# PMIC.net
KiCad netlist of a schematic drawn in Altium Designer
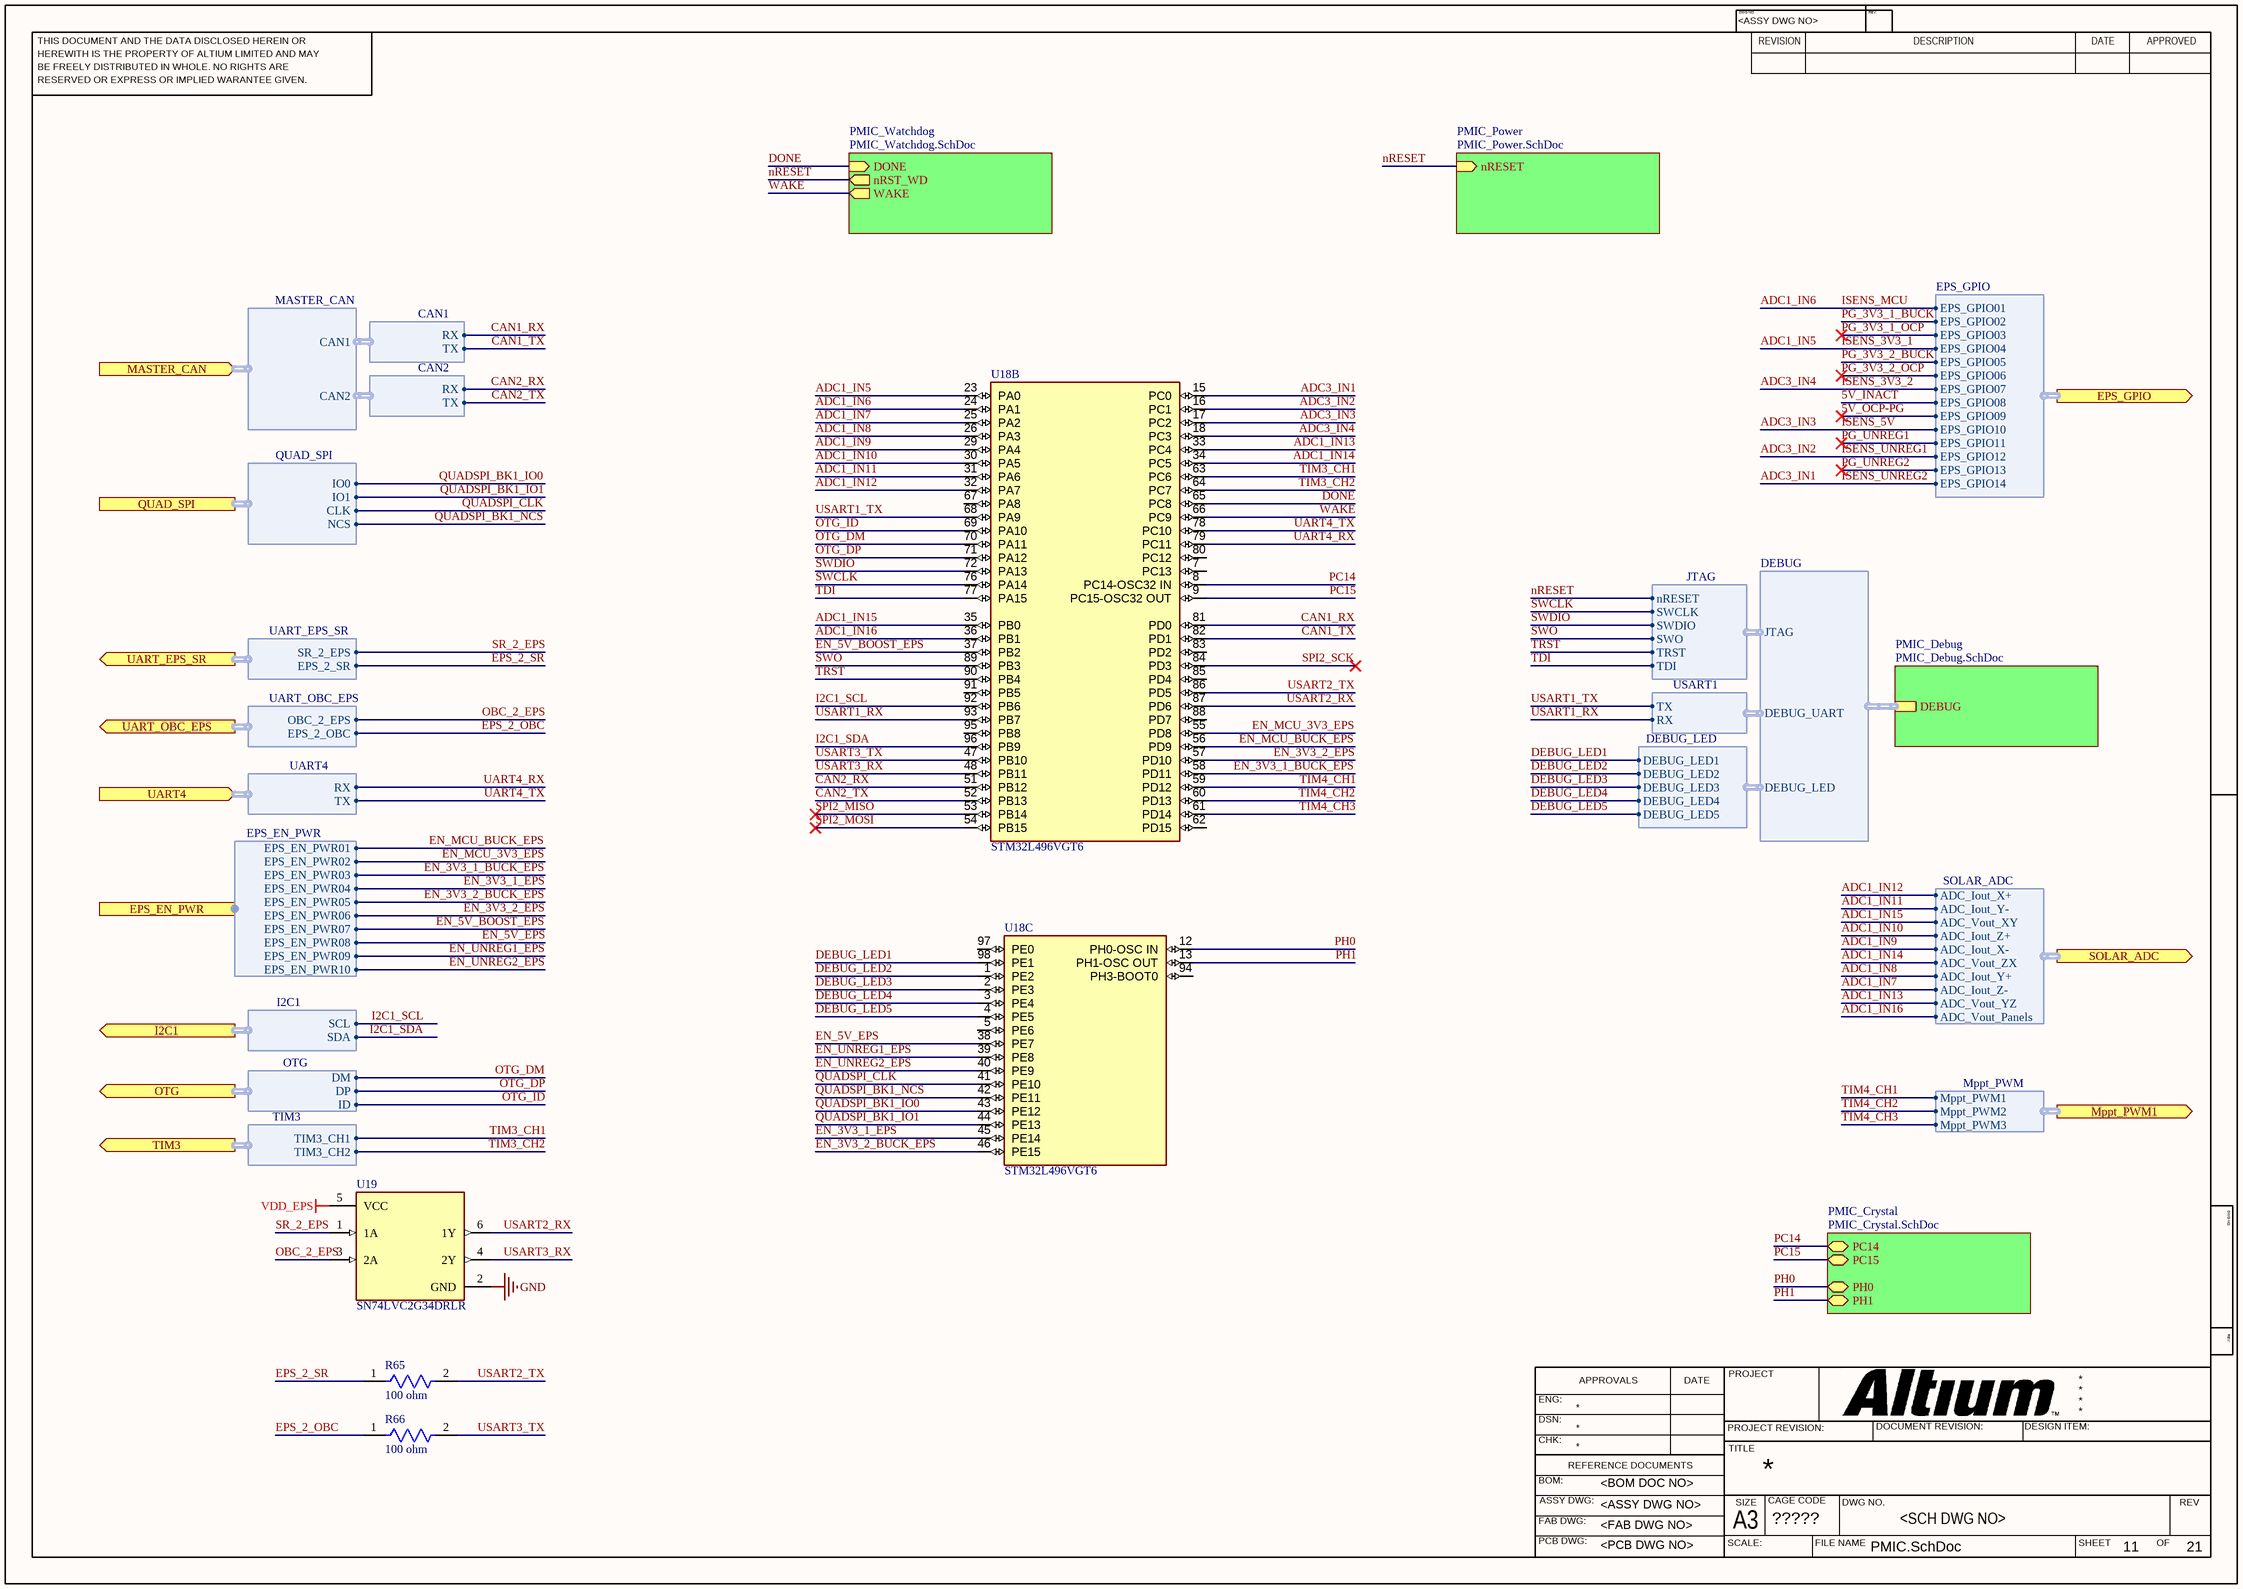
[diagram p0: PMIC.SchDoc]

(export (version "E")
  (design (tool "Eeschema 10.0.6"))
  (components
    (comp (ref "R65")
      (value "100 ohm")
      (footprint "FP-ERJP03-MFG")
      (description "ERJ-P03F1000V SMD Chip Resistor, 100 Ohm, ± 1%, 200 mW, 0603 [1608 Metric], Thick Film, Anti-Surge")
      (fields (field (name "TOLERANCE") "1%"))
      (libsource (lib "Altium Content Vault") (part "1029c3af85768c4190bb7ad29bc67b5"))
    )
    (comp (ref "R66")
      (value "100 ohm")
      (footprint "FP-ERJP03-MFG")
      (description "ERJ-P03F1000V SMD Chip Resistor, 100 Ohm, ± 1%, 200 mW, 0603 [1608 Metric], Thick Film, Anti-Surge")
      (fields (field (name "TOLERANCE") "1%"))
      (libsource (lib "Altium Content Vault") (part "1029c3af85768c4190bb7ad29bc67b5"))
    )
    (comp (ref "U18")
      (value "STM32L496VGT6")
      (footprint "FP-LQFP100-1L-MFG")
      (description "IC MCU 32BIT 1MB FLASH 100LQFP")
      (fields
        (field (name "MANUFACTURER") "STMicroelectronics")
        (field (name "OCTOPART") "https://octopart.com/stm32l496vgt6-stmicroelectronics-80826723")
      )
      (libsource (lib "Altium Content Vault") (part "c3654b0af0513536dfc3423c68ccd0e"))
    )
    (comp (ref "U19")
      (value "SN74LVC2G34DRLR")
      (footprint "FP-DRL0006A-MFG")
      (description "IC BUFFER NON-INVERT 5.5V 6SOT")
      (libsource (lib "Altium Content Vault") (part "59303bce76f5fafbc101ba271662c75"))
    )
  )
  (nets
    (net (code "21") (name "/ADC1_IN5") (class "Default")
      (node (ref "U18") (pin "23") (pinfunction "PA0_23") (pintype "bidirectional"))
    )
    (net (code "22") (name "/ADC1_IN6") (class "Default")
      (node (ref "U18") (pin "24") (pinfunction "PA1_24") (pintype "bidirectional"))
    )
    (net (code "23") (name "/ADC1_IN7") (class "Default")
      (node (ref "U18") (pin "25") (pinfunction "PA2_25") (pintype "bidirectional"))
    )
    (net (code "24") (name "/ADC1_IN8") (class "Default")
      (node (ref "U18") (pin "26") (pinfunction "PA3_26") (pintype "bidirectional"))
    )
    (net (code "25") (name "/ADC1_IN9") (class "Default")
      (node (ref "U18") (pin "29") (pinfunction "PA4_29") (pintype "bidirectional"))
    )
    (net (code "26") (name "/ADC1_IN10") (class "Default")
      (node (ref "U18") (pin "30") (pinfunction "PA5_30") (pintype "bidirectional"))
    )
    (net (code "27") (name "/ADC1_IN11") (class "Default")
      (node (ref "U18") (pin "31") (pinfunction "PA6_31") (pintype "bidirectional"))
    )
    (net (code "28") (name "/ADC1_IN12") (class "Default")
      (node (ref "U18") (pin "32") (pinfunction "PA7_32") (pintype "bidirectional"))
    )
    (net (code "29") (name "/ADC1_IN13") (class "Default")
      (node (ref "U18") (pin "33") (pinfunction "PC4_33") (pintype "bidirectional"))
    )
    (net (code "30") (name "/ADC1_IN14") (class "Default")
      (node (ref "U18") (pin "34") (pinfunction "PC5_34") (pintype "bidirectional"))
    )
    (net (code "31") (name "/ADC1_IN15") (class "Default")
      (node (ref "U18") (pin "35") (pinfunction "PB0_35") (pintype "bidirectional"))
    )
    (net (code "32") (name "/ADC1_IN16") (class "Default")
      (node (ref "U18") (pin "36") (pinfunction "PB1_36") (pintype "bidirectional"))
    )
    (net (code "33") (name "/ADC3_IN1") (class "Default")
      (node (ref "U18") (pin "15") (pinfunction "PC0_15") (pintype "bidirectional"))
    )
    (net (code "34") (name "/ADC3_IN2") (class "Default")
      (node (ref "U18") (pin "16") (pinfunction "PC1_16") (pintype "bidirectional"))
    )
    (net (code "35") (name "/ADC3_IN3") (class "Default")
      (node (ref "U18") (pin "17") (pinfunction "PC2_17") (pintype "bidirectional"))
    )
    (net (code "36") (name "/ADC3_IN4") (class "Default")
      (node (ref "U18") (pin "18") (pinfunction "PC3_18") (pintype "bidirectional"))
    )
    (net (code "37") (name "/CAN1_RX") (class "Default")
      (node (ref "U18") (pin "81") (pinfunction "PD0_81") (pintype "bidirectional"))
    )
    (net (code "38") (name "/CAN1_TX") (class "Default")
      (node (ref "U18") (pin "82") (pinfunction "PD1_82") (pintype "bidirectional"))
    )
    (net (code "39") (name "/CAN2_RX") (class "Default")
      (node (ref "U18") (pin "51") (pinfunction "PB12_51") (pintype "bidirectional"))
    )
    (net (code "40") (name "/CAN2_TX") (class "Default")
      (node (ref "U18") (pin "52") (pinfunction "PB13_52") (pintype "bidirectional"))
    )
    (net (code "41") (name "/DEBUG_LED1") (class "Default")
      (node (ref "U18") (pin "98") (pinfunction "PE1_98") (pintype "bidirectional"))
    )
    (net (code "42") (name "/DEBUG_LED2") (class "Default")
      (node (ref "U18") (pin "1") (pinfunction "PE2_1") (pintype "bidirectional"))
    )
    (net (code "43") (name "/DEBUG_LED3") (class "Default")
      (node (ref "U18") (pin "2") (pinfunction "PE3_2") (pintype "bidirectional"))
    )
    (net (code "44") (name "/DEBUG_LED4") (class "Default")
      (node (ref "U18") (pin "3") (pinfunction "PE4_3") (pintype "bidirectional"))
    )
    (net (code "45") (name "/DEBUG_LED5") (class "Default")
      (node (ref "U18") (pin "4") (pinfunction "PE5_4") (pintype "bidirectional"))
    )
    (net (code "46") (name "/DONE") (class "Default")
      (node (ref "U18") (pin "65") (pinfunction "PC8_65") (pintype "bidirectional"))
    )
    (net (code "47") (name "/EN_3V3_1_BUCK_EPS") (class "Default")
      (node (ref "U18") (pin "58") (pinfunction "PD11_58") (pintype "bidirectional"))
    )
    (net (code "48") (name "/EN_3V3_1_EPS") (class "Default")
      (node (ref "U18") (pin "45") (pinfunction "PE14_45") (pintype "bidirectional"))
    )
    (net (code "49") (name "/EN_3V3_2_BUCK_EPS") (class "Default")
      (node (ref "U18") (pin "46") (pinfunction "PE15_46") (pintype "bidirectional"))
    )
    (net (code "50") (name "/EN_3V3_2_EPS") (class "Default")
      (node (ref "U18") (pin "57") (pinfunction "PD10_57") (pintype "bidirectional"))
    )
    (net (code "51") (name "/EN_5V_BOOST_EPS") (class "Default")
      (node (ref "U18") (pin "37") (pinfunction "PB2_37") (pintype "bidirectional"))
    )
    (net (code "52") (name "/EN_5V_EPS") (class "Default")
      (node (ref "U18") (pin "38") (pinfunction "PE7_38") (pintype "bidirectional"))
    )
    (net (code "53") (name "/EN_MCU_3V3_EPS") (class "Default")
      (node (ref "U18") (pin "55") (pinfunction "PD8_55") (pintype "bidirectional"))
    )
    (net (code "54") (name "/EN_MCU_BUCK_EPS") (class "Default")
      (node (ref "U18") (pin "56") (pinfunction "PD9_56") (pintype "bidirectional"))
    )
    (net (code "55") (name "/EN_UNREG1_EPS") (class "Default")
      (node (ref "U18") (pin "39") (pinfunction "PE8_39") (pintype "bidirectional"))
    )
    (net (code "56") (name "/EN_UNREG2_EPS") (class "Default")
      (node (ref "U18") (pin "40") (pinfunction "PE9_40") (pintype "bidirectional"))
    )
    (net (code "57") (name "/EPS_2_OBC") (class "Default")
      (node (ref "R66") (pin "1") (pinfunction "1_1") (pintype "passive"))
    )
    (net (code "58") (name "/EPS_2_SR") (class "Default")
      (node (ref "R65") (pin "1") (pinfunction "1_1") (pintype "passive"))
    )
    (net (code "59") (name "/I2C1_SCL") (class "Default")
      (node (ref "U18") (pin "92") (pinfunction "PB6_92") (pintype "bidirectional"))
    )
    (net (code "60") (name "/I2C1_SDA") (class "Default")
      (node (ref "U18") (pin "96") (pinfunction "PB9_96") (pintype "bidirectional"))
    )
    (net (code "62") (name "/OBC_2_EPS") (class "Default")
      (node (ref "U19") (pin "3") (pinfunction "2A_3") (pintype "input"))
    )
    (net (code "63") (name "/OTG_DM") (class "Default")
      (node (ref "U18") (pin "70") (pinfunction "PA11_70") (pintype "bidirectional"))
    )
    (net (code "64") (name "/OTG_DP") (class "Default")
      (node (ref "U18") (pin "71") (pinfunction "PA12_71") (pintype "bidirectional"))
    )
    (net (code "65") (name "/OTG_ID") (class "Default")
      (node (ref "U18") (pin "69") (pinfunction "PA10_69") (pintype "bidirectional"))
    )
    (net (code "66") (name "/PC14") (class "Default")
      (node (ref "U18") (pin "8") (pinfunction "PC14-OSC32_IN_8") (pintype "bidirectional"))
    )
    (net (code "67") (name "/PC15") (class "Default")
      (node (ref "U18") (pin "9") (pinfunction "PC15-OSC32_OUT_9") (pintype "bidirectional"))
    )
    (net (code "74") (name "/PH0") (class "Default")
      (node (ref "U18") (pin "12") (pinfunction "PH0-OSC_IN_12") (pintype "bidirectional"))
    )
    (net (code "75") (name "/PH1") (class "Default")
      (node (ref "U18") (pin "13") (pinfunction "PH1-OSC_OUT_13") (pintype "bidirectional"))
    )
    (net (code "76") (name "/QUADSPI_BK1_IO0") (class "Default")
      (node (ref "U18") (pin "43") (pinfunction "PE12_43") (pintype "bidirectional"))
    )
    (net (code "77") (name "/QUADSPI_BK1_IO1") (class "Default")
      (node (ref "U18") (pin "44") (pinfunction "PE13_44") (pintype "bidirectional"))
    )
    (net (code "78") (name "/QUADSPI_BK1_NCS") (class "Default")
      (node (ref "U18") (pin "42") (pinfunction "PE11_42") (pintype "bidirectional"))
    )
    (net (code "79") (name "/QUADSPI_CLK") (class "Default")
      (node (ref "U18") (pin "41") (pinfunction "PE10_41") (pintype "bidirectional"))
    )
    (net (code "80") (name "/SPI2_MISO") (class "Default")
      (node (ref "U18") (pin "53") (pinfunction "PB14_53") (pintype "bidirectional+no_connect"))
    )
    (net (code "81") (name "/SPI2_MOSI") (class "Default")
      (node (ref "U18") (pin "54") (pinfunction "PB15_54") (pintype "bidirectional+no_connect"))
    )
    (net (code "82") (name "/SPI2_SCK") (class "Default")
      (node (ref "U18") (pin "84") (pinfunction "PD3_84") (pintype "bidirectional+no_connect"))
    )
    (net (code "83") (name "/SR_2_EPS") (class "Default")
      (node (ref "U19") (pin "1") (pinfunction "1A_1") (pintype "input"))
    )
    (net (code "84") (name "/SWCLK") (class "Default")
      (node (ref "U18") (pin "76") (pinfunction "PA14_76") (pintype "bidirectional"))
    )
    (net (code "85") (name "/SWDIO") (class "Default")
      (node (ref "U18") (pin "72") (pinfunction "PA13_72") (pintype "bidirectional"))
    )
    (net (code "86") (name "/SWO") (class "Default")
      (node (ref "U18") (pin "89") (pinfunction "PB3_89") (pintype "bidirectional"))
    )
    (net (code "87") (name "/TDI") (class "Default")
      (node (ref "U18") (pin "77") (pinfunction "PA15_77") (pintype "bidirectional"))
    )
    (net (code "88") (name "/TIM3_CH1") (class "Default")
      (node (ref "U18") (pin "63") (pinfunction "PC6_63") (pintype "bidirectional"))
    )
    (net (code "89") (name "/TIM3_CH2") (class "Default")
      (node (ref "U18") (pin "64") (pinfunction "PC7_64") (pintype "bidirectional"))
    )
    (net (code "90") (name "/TIM4_CH1") (class "Default")
      (node (ref "U18") (pin "59") (pinfunction "PD12_59") (pintype "bidirectional"))
    )
    (net (code "91") (name "/TIM4_CH2") (class "Default")
      (node (ref "U18") (pin "60") (pinfunction "PD13_60") (pintype "bidirectional"))
    )
    (net (code "92") (name "/TIM4_CH3") (class "Default")
      (node (ref "U18") (pin "61") (pinfunction "PD14_61") (pintype "bidirectional"))
    )
    (net (code "93") (name "/TRST") (class "Default")
      (node (ref "U18") (pin "90") (pinfunction "PB4_90") (pintype "bidirectional"))
    )
    (net (code "94") (name "/UART4_RX") (class "Default")
      (node (ref "U18") (pin "79") (pinfunction "PC11_79") (pintype "bidirectional"))
    )
    (net (code "95") (name "/UART4_TX") (class "Default")
      (node (ref "U18") (pin "78") (pinfunction "PC10_78") (pintype "bidirectional"))
    )
    (net (code "96") (name "/USART1_RX") (class "Default")
      (node (ref "U18") (pin "93") (pinfunction "PB7_93") (pintype "bidirectional"))
    )
    (net (code "97") (name "/USART1_TX") (class "Default")
      (node (ref "U18") (pin "68") (pinfunction "PA9_68") (pintype "bidirectional"))
    )
    (net (code "98") (name "/USART2_RX") (class "Default")
      (node (ref "U18") (pin "87") (pinfunction "PD6_87") (pintype "bidirectional"))
      (node (ref "U19") (pin "6") (pinfunction "1Y_6") (pintype "output"))
    )
    (net (code "99") (name "/USART2_TX") (class "Default")
      (node (ref "R65") (pin "2") (pinfunction "2_2") (pintype "passive"))
      (node (ref "U18") (pin "86") (pinfunction "PD5_86") (pintype "bidirectional"))
    )
    (net (code "100") (name "/USART3_RX") (class "Default")
      (node (ref "U18") (pin "48") (pinfunction "PB11_48") (pintype "bidirectional"))
      (node (ref "U19") (pin "4") (pinfunction "2Y_4") (pintype "output"))
    )
    (net (code "101") (name "/USART3_TX") (class "Default")
      (node (ref "R66") (pin "2") (pinfunction "2_2") (pintype "passive"))
      (node (ref "U18") (pin "47") (pinfunction "PB10_47") (pintype "bidirectional"))
    )
    (net (code "102") (name "/WAKE") (class "Default")
      (node (ref "U18") (pin "66") (pinfunction "PC9_66") (pintype "bidirectional"))
    )
    (net (code "121") (name "GND") (class "Default")
      (node (ref "U19") (pin "2") (pinfunction "GND_2") (pintype "power_in"))
    )
    (net (code "122") (name "VDD_EPS") (class "Default")
      (node (ref "U19") (pin "5") (pinfunction "VCC_5") (pintype "power_in"))
    )
    (net (code "123") (name "unconnected-(U18B-PA8-Pad67)") (class "Default")
      (node (ref "U18") (pin "67") (pinfunction "PA8_67") (pintype "bidirectional"))
    )
    (net (code "124") (name "unconnected-(U18B-PB5-Pad91)") (class "Default")
      (node (ref "U18") (pin "91") (pinfunction "PB5_91") (pintype "bidirectional"))
    )
    (net (code "125") (name "unconnected-(U18B-PB8-Pad95)") (class "Default")
      (node (ref "U18") (pin "95") (pinfunction "PB8_95") (pintype "bidirectional"))
    )
    (net (code "126") (name "unconnected-(U18B-PC12-Pad80)") (class "Default")
      (node (ref "U18") (pin "80") (pinfunction "PC12_80") (pintype "bidirectional"))
    )
    (net (code "127") (name "unconnected-(U18B-PC13-Pad7)") (class "Default")
      (node (ref "U18") (pin "7") (pinfunction "PC13_7") (pintype "bidirectional"))
    )
    (net (code "128") (name "unconnected-(U18B-PD2-Pad83)") (class "Default")
      (node (ref "U18") (pin "83") (pinfunction "PD2_83") (pintype "bidirectional"))
    )
    (net (code "129") (name "unconnected-(U18B-PD4-Pad85)") (class "Default")
      (node (ref "U18") (pin "85") (pinfunction "PD4_85") (pintype "bidirectional"))
    )
    (net (code "130") (name "unconnected-(U18B-PD7-Pad88)") (class "Default")
      (node (ref "U18") (pin "88") (pinfunction "PD7_88") (pintype "bidirectional"))
    )
    (net (code "131") (name "unconnected-(U18B-PD15-Pad62)") (class "Default")
      (node (ref "U18") (pin "62") (pinfunction "PD15_62") (pintype "bidirectional"))
    )
    (net (code "132") (name "unconnected-(U18C-PE0-Pad97)") (class "Default")
      (node (ref "U18") (pin "97") (pinfunction "PE0_97") (pintype "bidirectional"))
    )
    (net (code "133") (name "unconnected-(U18C-PE6-Pad5)") (class "Default")
      (node (ref "U18") (pin "5") (pinfunction "PE6_5") (pintype "bidirectional"))
    )
    (net (code "134") (name "unconnected-(U18C-PH3-BOOT0-Pad94)") (class "Default")
      (node (ref "U18") (pin "94") (pinfunction "PH3-BOOT0_94") (pintype "bidirectional"))
    )
  )
)
